# Sheet2.net
KiCad netlist of a schematic drawn in Altium Designer
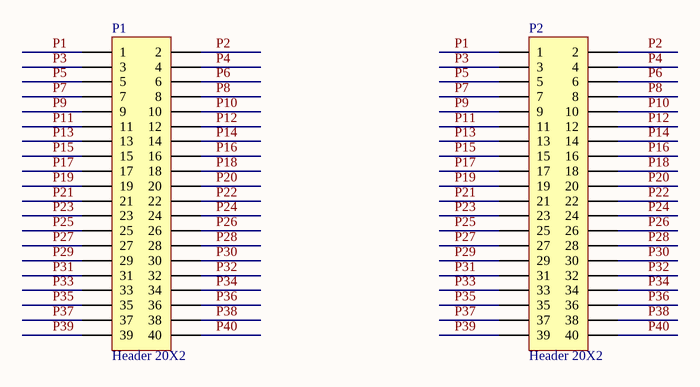
[diagram p0: Sheet2.SchDoc]

(export (version "E")
  (design (tool "Eeschema 10.0.6"))
  (components
    (comp (ref "P1")
      (value "Header 20X2")
      (footprint "P40Con2mm")
      (description "Header, 20-Pin, Dual row")
      (fields (field (name "PUBLISHER") "Altium Limited"))
      (libsource (lib "Miscellaneous Connectors") (part "Header 20X2"))
    )
    (comp (ref "P2")
      (value "Header 20X2")
      (footprint "BTB0.8con40Pin")
      (description "Header, 20-Pin, Dual row")
      (fields (field (name "PUBLISHER") "Altium Limited"))
      (libsource (lib "Miscellaneous Connectors") (part "Header 20X2"))
    )
  )
  (nets
    (net (code "1") (name "/P1") (class "Default")
      (node (ref "P1") (pin "1") (pinfunction "1_1") (pintype "passive"))
      (node (ref "P2") (pin "1") (pinfunction "1_1") (pintype "passive"))
    )
    (net (code "2") (name "/P2") (class "Default")
      (node (ref "P1") (pin "2") (pinfunction "2_2") (pintype "passive"))
      (node (ref "P2") (pin "2") (pinfunction "2_2") (pintype "passive"))
    )
    (net (code "3") (name "/P3") (class "Default")
      (node (ref "P1") (pin "3") (pinfunction "3_3") (pintype "passive"))
      (node (ref "P2") (pin "3") (pinfunction "3_3") (pintype "passive"))
    )
    (net (code "4") (name "/P4") (class "Default")
      (node (ref "P1") (pin "4") (pinfunction "4_4") (pintype "passive"))
      (node (ref "P2") (pin "4") (pinfunction "4_4") (pintype "passive"))
    )
    (net (code "5") (name "/P5") (class "Default")
      (node (ref "P1") (pin "5") (pinfunction "5_5") (pintype "passive"))
      (node (ref "P2") (pin "5") (pinfunction "5_5") (pintype "passive"))
    )
    (net (code "6") (name "/P6") (class "Default")
      (node (ref "P1") (pin "6") (pinfunction "6_6") (pintype "passive"))
      (node (ref "P2") (pin "6") (pinfunction "6_6") (pintype "passive"))
    )
    (net (code "7") (name "/P7") (class "Default")
      (node (ref "P1") (pin "7") (pinfunction "7_7") (pintype "passive"))
      (node (ref "P2") (pin "7") (pinfunction "7_7") (pintype "passive"))
    )
    (net (code "8") (name "/P8") (class "Default")
      (node (ref "P1") (pin "8") (pinfunction "8_8") (pintype "passive"))
      (node (ref "P2") (pin "8") (pinfunction "8_8") (pintype "passive"))
    )
    (net (code "9") (name "/P9") (class "Default")
      (node (ref "P1") (pin "9") (pinfunction "9_9") (pintype "passive"))
      (node (ref "P2") (pin "9") (pinfunction "9_9") (pintype "passive"))
    )
    (net (code "10") (name "/P10") (class "Default")
      (node (ref "P1") (pin "10") (pinfunction "10_10") (pintype "passive"))
      (node (ref "P2") (pin "10") (pinfunction "10_10") (pintype "passive"))
    )
    (net (code "11") (name "/P11") (class "Default")
      (node (ref "P1") (pin "11") (pinfunction "11_11") (pintype "passive"))
      (node (ref "P2") (pin "11") (pinfunction "11_11") (pintype "passive"))
    )
    (net (code "12") (name "/P12") (class "Default")
      (node (ref "P1") (pin "12") (pinfunction "12_12") (pintype "passive"))
      (node (ref "P2") (pin "12") (pinfunction "12_12") (pintype "passive"))
    )
    (net (code "13") (name "/P13") (class "Default")
      (node (ref "P1") (pin "13") (pinfunction "13_13") (pintype "passive"))
      (node (ref "P2") (pin "13") (pinfunction "13_13") (pintype "passive"))
    )
    (net (code "14") (name "/P14") (class "Default")
      (node (ref "P1") (pin "14") (pinfunction "14_14") (pintype "passive"))
      (node (ref "P2") (pin "14") (pinfunction "14_14") (pintype "passive"))
    )
    (net (code "15") (name "/P15") (class "Default")
      (node (ref "P1") (pin "15") (pinfunction "15_15") (pintype "passive"))
      (node (ref "P2") (pin "15") (pinfunction "15_15") (pintype "passive"))
    )
    (net (code "16") (name "/P16") (class "Default")
      (node (ref "P1") (pin "16") (pinfunction "16_16") (pintype "passive"))
      (node (ref "P2") (pin "16") (pinfunction "16_16") (pintype "passive"))
    )
    (net (code "17") (name "/P17") (class "Default")
      (node (ref "P1") (pin "17") (pinfunction "17_17") (pintype "passive"))
      (node (ref "P2") (pin "17") (pinfunction "17_17") (pintype "passive"))
    )
    (net (code "18") (name "/P18") (class "Default")
      (node (ref "P1") (pin "18") (pinfunction "18_18") (pintype "passive"))
      (node (ref "P2") (pin "18") (pinfunction "18_18") (pintype "passive"))
    )
    (net (code "19") (name "/P19") (class "Default")
      (node (ref "P1") (pin "19") (pinfunction "19_19") (pintype "passive"))
      (node (ref "P2") (pin "19") (pinfunction "19_19") (pintype "passive"))
    )
    (net (code "20") (name "/P20") (class "Default")
      (node (ref "P1") (pin "20") (pinfunction "20_20") (pintype "passive"))
      (node (ref "P2") (pin "20") (pinfunction "20_20") (pintype "passive"))
    )
    (net (code "21") (name "/P21") (class "Default")
      (node (ref "P1") (pin "21") (pinfunction "21_21") (pintype "passive"))
      (node (ref "P2") (pin "21") (pinfunction "21_21") (pintype "passive"))
    )
    (net (code "22") (name "/P22") (class "Default")
      (node (ref "P1") (pin "22") (pinfunction "22_22") (pintype "passive"))
      (node (ref "P2") (pin "22") (pinfunction "22_22") (pintype "passive"))
    )
    (net (code "23") (name "/P23") (class "Default")
      (node (ref "P1") (pin "23") (pinfunction "23_23") (pintype "passive"))
      (node (ref "P2") (pin "23") (pinfunction "23_23") (pintype "passive"))
    )
    (net (code "24") (name "/P24") (class "Default")
      (node (ref "P1") (pin "24") (pinfunction "24_24") (pintype "passive"))
      (node (ref "P2") (pin "24") (pinfunction "24_24") (pintype "passive"))
    )
    (net (code "25") (name "/P25") (class "Default")
      (node (ref "P1") (pin "25") (pinfunction "25_25") (pintype "passive"))
      (node (ref "P2") (pin "25") (pinfunction "25_25") (pintype "passive"))
    )
    (net (code "26") (name "/P26") (class "Default")
      (node (ref "P1") (pin "26") (pinfunction "26_26") (pintype "passive"))
      (node (ref "P2") (pin "26") (pinfunction "26_26") (pintype "passive"))
    )
    (net (code "27") (name "/P27") (class "Default")
      (node (ref "P1") (pin "27") (pinfunction "27_27") (pintype "passive"))
      (node (ref "P2") (pin "27") (pinfunction "27_27") (pintype "passive"))
    )
    (net (code "28") (name "/P28") (class "Default")
      (node (ref "P1") (pin "28") (pinfunction "28_28") (pintype "passive"))
      (node (ref "P2") (pin "28") (pinfunction "28_28") (pintype "passive"))
    )
    (net (code "29") (name "/P29") (class "Default")
      (node (ref "P1") (pin "29") (pinfunction "29_29") (pintype "passive"))
      (node (ref "P2") (pin "29") (pinfunction "29_29") (pintype "passive"))
    )
    (net (code "30") (name "/P30") (class "Default")
      (node (ref "P1") (pin "30") (pinfunction "30_30") (pintype "passive"))
      (node (ref "P2") (pin "30") (pinfunction "30_30") (pintype "passive"))
    )
    (net (code "31") (name "/P31") (class "Default")
      (node (ref "P1") (pin "31") (pinfunction "31_31") (pintype "passive"))
      (node (ref "P2") (pin "31") (pinfunction "31_31") (pintype "passive"))
    )
    (net (code "32") (name "/P32") (class "Default")
      (node (ref "P1") (pin "32") (pinfunction "32_32") (pintype "passive"))
      (node (ref "P2") (pin "32") (pinfunction "32_32") (pintype "passive"))
    )
    (net (code "33") (name "/P33") (class "Default")
      (node (ref "P1") (pin "33") (pinfunction "33_33") (pintype "passive"))
      (node (ref "P2") (pin "33") (pinfunction "33_33") (pintype "passive"))
    )
    (net (code "34") (name "/P34") (class "Default")
      (node (ref "P1") (pin "34") (pinfunction "34_34") (pintype "passive"))
      (node (ref "P2") (pin "34") (pinfunction "34_34") (pintype "passive"))
    )
    (net (code "35") (name "/P35") (class "Default")
      (node (ref "P1") (pin "35") (pinfunction "35_35") (pintype "passive"))
      (node (ref "P2") (pin "35") (pinfunction "35_35") (pintype "passive"))
    )
    (net (code "36") (name "/P36") (class "Default")
      (node (ref "P1") (pin "36") (pinfunction "36_36") (pintype "passive"))
      (node (ref "P2") (pin "36") (pinfunction "36_36") (pintype "passive"))
    )
    (net (code "37") (name "/P37") (class "Default")
      (node (ref "P1") (pin "37") (pinfunction "37_37") (pintype "passive"))
      (node (ref "P2") (pin "37") (pinfunction "37_37") (pintype "passive"))
    )
    (net (code "38") (name "/P38") (class "Default")
      (node (ref "P1") (pin "38") (pinfunction "38_38") (pintype "passive"))
      (node (ref "P2") (pin "38") (pinfunction "38_38") (pintype "passive"))
    )
    (net (code "39") (name "/P39") (class "Default")
      (node (ref "P1") (pin "39") (pinfunction "39_39") (pintype "passive"))
      (node (ref "P2") (pin "39") (pinfunction "39_39") (pintype "passive"))
    )
    (net (code "40") (name "/P40") (class "Default")
      (node (ref "P1") (pin "40") (pinfunction "40_40") (pintype "passive"))
      (node (ref "P2") (pin "40") (pinfunction "40_40") (pintype "passive"))
    )
  )
)
